# I2C_SW.net
KiCad netlist of a schematic drawn in Altium Designer
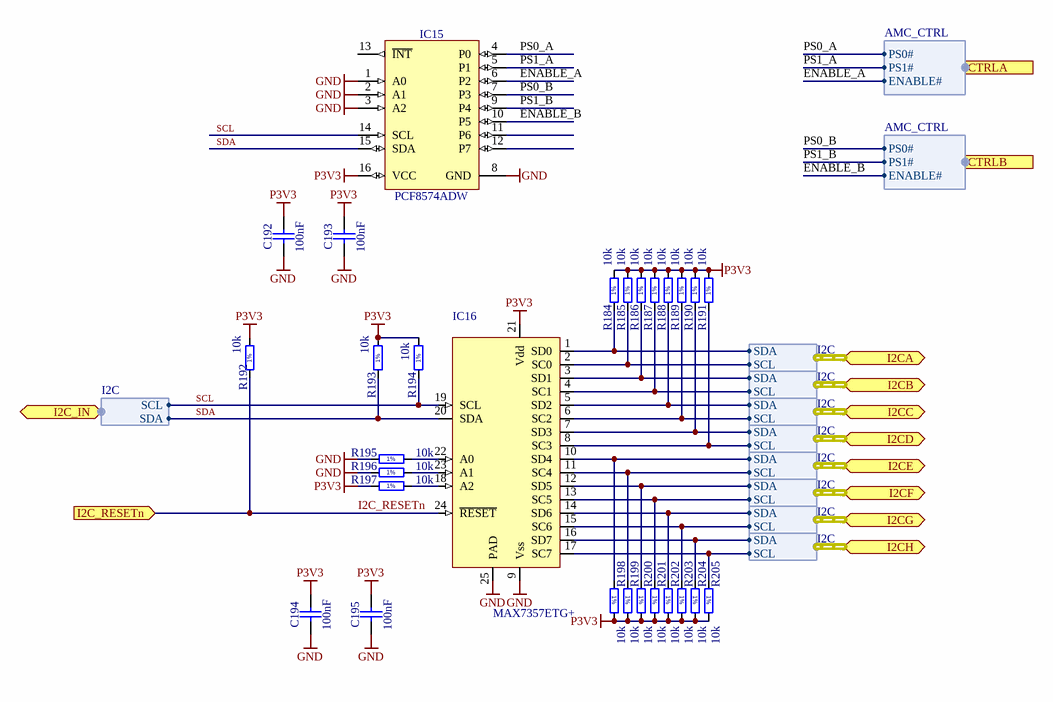
[diagram p0: I2C_SW.SchDoc]

(export (version "E")
  (design (tool "Eeschema 10.0.6"))
  (components
    (comp (ref "C192")
      (value "100nF")
      (footprint "CAPC0603X33N")
      (description "Non-polarised capacitor")
      (fields
        (field (name "PART NUMBER") "CC0201_100NF_6.3V_10%_X5R")
        (field (name "VOLTAGE") "6.3V")
        (field (name "AUTHOR") "CERN DEM JLC")
      )
      (libsource (lib "Capacitors") (part "Capacitor - non polarized"))
    )
    (comp (ref "C193")
      (value "100nF")
      (footprint "CAPC0603X33N")
      (description "Non-polarised capacitor")
      (fields
        (field (name "PART NUMBER") "CC0201_100NF_6.3V_10%_X5R")
        (field (name "VOLTAGE") "6.3V")
        (field (name "AUTHOR") "CERN DEM JLC")
      )
      (libsource (lib "Capacitors") (part "Capacitor - non polarized"))
    )
    (comp (ref "C194")
      (value "100nF")
      (footprint "CAPC0603X33N")
      (description "Non-polarised capacitor")
      (fields
        (field (name "PART NUMBER") "CC0201_100NF_6.3V_10%_X5R")
        (field (name "VOLTAGE") "6.3V")
        (field (name "AUTHOR") "CERN DEM JLC")
      )
      (libsource (lib "Capacitors") (part "Capacitor - non polarized"))
    )
    (comp (ref "C195")
      (value "100nF")
      (footprint "CAPC0603X33N")
      (description "Non-polarised capacitor")
      (fields
        (field (name "PART NUMBER") "CC0201_100NF_6.3V_10%_X5R")
        (field (name "VOLTAGE") "6.3V")
        (field (name "AUTHOR") "CERN DEM JLC")
      )
      (libsource (lib "Capacitors") (part "Capacitor - non polarized"))
    )
    (comp (ref "IC15")
      (value "PCF8574ADW")
      (footprint "SOIC127P1030X265-16N")
      (description "Remote 8-bit I/O Expander For I2C Bus")
      (fields (field (name "MANUFACTURER") "TEXAS INSTRUMENTS") (field (name "AUTHOR") "CERN DEM JLC"))
      (libsource (lib "ICs And Semiconductors") (part "PCF8574ADW"))
    )
    (comp (ref "IC16")
      (value "MAX7357ETG+")
      (footprint "HVQFN24")
      (description "8-channel I2C-bus multiplexer with reset, INT and timeout")
      (libsource (lib "LIBRARY_SCH") (part "IIC_MUX_MAX7357ETG+"))
    )
    (comp (ref "R184")
      (value "10k")
      (footprint "RESC1005X40N")
      (description "Resistor - 1%")
      (fields
        (field (name "PART NUMBER") "R0402_10K_1%_0.0625W_100PPM")
        (field (name "POWER") "0.0625W")
        (field (name "AUTHOR") "CERN DEM JLC")
      )
      (libsource (lib "Resistors") (part "Resistor - 1%"))
    )
    (comp (ref "R185")
      (value "10k")
      (footprint "RESC1005X40N")
      (description "Resistor - 1%")
      (fields
        (field (name "PART NUMBER") "R0402_10K_1%_0.0625W_100PPM")
        (field (name "POWER") "0.0625W")
        (field (name "AUTHOR") "CERN DEM JLC")
      )
      (libsource (lib "Resistors") (part "Resistor - 1%"))
    )
    (comp (ref "R186")
      (value "10k")
      (footprint "RESC1005X40N")
      (description "Resistor - 1%")
      (fields
        (field (name "PART NUMBER") "R0402_10K_1%_0.0625W_100PPM")
        (field (name "POWER") "0.0625W")
        (field (name "AUTHOR") "CERN DEM JLC")
      )
      (libsource (lib "Resistors") (part "Resistor - 1%"))
    )
    (comp (ref "R187")
      (value "10k")
      (footprint "RESC1005X40N")
      (description "Resistor - 1%")
      (fields
        (field (name "PART NUMBER") "R0402_10K_1%_0.0625W_100PPM")
        (field (name "POWER") "0.0625W")
        (field (name "AUTHOR") "CERN DEM JLC")
      )
      (libsource (lib "Resistors") (part "Resistor - 1%"))
    )
    (comp (ref "R188")
      (value "10k")
      (footprint "RESC1005X40N")
      (description "Resistor - 1%")
      (fields
        (field (name "PART NUMBER") "R0402_10K_1%_0.0625W_100PPM")
        (field (name "POWER") "0.0625W")
        (field (name "AUTHOR") "CERN DEM JLC")
      )
      (libsource (lib "Resistors") (part "Resistor - 1%"))
    )
    (comp (ref "R189")
      (value "10k")
      (footprint "RESC1005X40N")
      (description "Resistor - 1%")
      (fields
        (field (name "PART NUMBER") "R0402_10K_1%_0.0625W_100PPM")
        (field (name "POWER") "0.0625W")
        (field (name "AUTHOR") "CERN DEM JLC")
      )
      (libsource (lib "Resistors") (part "Resistor - 1%"))
    )
    (comp (ref "R190")
      (value "10k")
      (footprint "RESC1005X40N")
      (description "Resistor - 1%")
      (fields
        (field (name "PART NUMBER") "R0402_10K_1%_0.0625W_100PPM")
        (field (name "POWER") "0.0625W")
        (field (name "AUTHOR") "CERN DEM JLC")
      )
      (libsource (lib "Resistors") (part "Resistor - 1%"))
    )
    (comp (ref "R191")
      (value "10k")
      (footprint "RESC1005X40N")
      (description "Resistor - 1%")
      (fields
        (field (name "PART NUMBER") "R0402_10K_1%_0.0625W_100PPM")
        (field (name "POWER") "0.0625W")
        (field (name "AUTHOR") "CERN DEM JLC")
      )
      (libsource (lib "Resistors") (part "Resistor - 1%"))
    )
    (comp (ref "R192")
      (value "10k")
      (footprint "RESC1005X40N")
      (description "Resistor - 1%")
      (fields
        (field (name "PART NUMBER") "R0402_10K_1%_0.0625W_100PPM")
        (field (name "POWER") "0.0625W")
        (field (name "AUTHOR") "CERN DEM JLC")
      )
      (libsource (lib "Resistors") (part "Resistor - 1%"))
    )
    (comp (ref "R193")
      (value "10k")
      (footprint "RESC1005X40N")
      (description "Resistor - 1%")
      (fields
        (field (name "PART NUMBER") "R0402_10K_1%_0.0625W_100PPM")
        (field (name "POWER") "0.0625W")
        (field (name "AUTHOR") "CERN DEM JLC")
      )
      (libsource (lib "Resistors") (part "Resistor - 1%"))
    )
    (comp (ref "R194")
      (value "10k")
      (footprint "RESC1005X40N")
      (description "Resistor - 1%")
      (fields
        (field (name "PART NUMBER") "R0402_10K_1%_0.0625W_100PPM")
        (field (name "POWER") "0.0625W")
        (field (name "AUTHOR") "CERN DEM JLC")
      )
      (libsource (lib "Resistors") (part "Resistor - 1%"))
    )
    (comp (ref "R195")
      (value "10k")
      (footprint "RESC1005X40N")
      (description "Resistor - 1%")
      (fields
        (field (name "PART NUMBER") "R0402_10K_1%_0.0625W_100PPM")
        (field (name "POWER") "0.0625W")
        (field (name "AUTHOR") "CERN DEM JLC")
      )
      (libsource (lib "Resistors") (part "Resistor - 1%"))
    )
    (comp (ref "R196")
      (value "10k")
      (footprint "RESC1005X40N")
      (description "Resistor - 1%")
      (fields
        (field (name "PART NUMBER") "R0402_10K_1%_0.0625W_100PPM")
        (field (name "POWER") "0.0625W")
        (field (name "AUTHOR") "CERN DEM JLC")
      )
      (libsource (lib "Resistors") (part "Resistor - 1%"))
    )
    (comp (ref "R197")
      (value "10k")
      (footprint "RESC1005X40N")
      (description "Resistor - 1%")
      (fields
        (field (name "PART NUMBER") "R0402_10K_1%_0.0625W_100PPM")
        (field (name "POWER") "0.0625W")
        (field (name "AUTHOR") "CERN DEM JLC")
      )
      (libsource (lib "Resistors") (part "Resistor - 1%"))
    )
    (comp (ref "R198")
      (value "10k")
      (footprint "RESC1005X40N")
      (description "Resistor - 1%")
      (fields
        (field (name "PART NUMBER") "R0402_10K_1%_0.0625W_100PPM")
        (field (name "POWER") "0.0625W")
        (field (name "AUTHOR") "CERN DEM JLC")
      )
      (libsource (lib "Resistors") (part "Resistor - 1%"))
    )
    (comp (ref "R199")
      (value "10k")
      (footprint "RESC1005X40N")
      (description "Resistor - 1%")
      (fields
        (field (name "PART NUMBER") "R0402_10K_1%_0.0625W_100PPM")
        (field (name "POWER") "0.0625W")
        (field (name "AUTHOR") "CERN DEM JLC")
      )
      (libsource (lib "Resistors") (part "Resistor - 1%"))
    )
    (comp (ref "R200")
      (value "10k")
      (footprint "RESC1005X40N")
      (description "Resistor - 1%")
      (fields
        (field (name "PART NUMBER") "R0402_10K_1%_0.0625W_100PPM")
        (field (name "POWER") "0.0625W")
        (field (name "AUTHOR") "CERN DEM JLC")
      )
      (libsource (lib "Resistors") (part "Resistor - 1%"))
    )
    (comp (ref "R201")
      (value "10k")
      (footprint "RESC1005X40N")
      (description "Resistor - 1%")
      (fields
        (field (name "PART NUMBER") "R0402_10K_1%_0.0625W_100PPM")
        (field (name "POWER") "0.0625W")
        (field (name "AUTHOR") "CERN DEM JLC")
      )
      (libsource (lib "Resistors") (part "Resistor - 1%"))
    )
    (comp (ref "R202")
      (value "10k")
      (footprint "RESC1005X40N")
      (description "Resistor - 1%")
      (fields
        (field (name "PART NUMBER") "R0402_10K_1%_0.0625W_100PPM")
        (field (name "POWER") "0.0625W")
        (field (name "AUTHOR") "CERN DEM JLC")
      )
      (libsource (lib "Resistors") (part "Resistor - 1%"))
    )
    (comp (ref "R203")
      (value "10k")
      (footprint "RESC1005X40N")
      (description "Resistor - 1%")
      (fields
        (field (name "PART NUMBER") "R0402_10K_1%_0.0625W_100PPM")
        (field (name "POWER") "0.0625W")
        (field (name "AUTHOR") "CERN DEM JLC")
      )
      (libsource (lib "Resistors") (part "Resistor - 1%"))
    )
    (comp (ref "R204")
      (value "10k")
      (footprint "RESC1005X40N")
      (description "Resistor - 1%")
      (fields
        (field (name "PART NUMBER") "R0402_10K_1%_0.0625W_100PPM")
        (field (name "POWER") "0.0625W")
        (field (name "AUTHOR") "CERN DEM JLC")
      )
      (libsource (lib "Resistors") (part "Resistor - 1%"))
    )
    (comp (ref "R205")
      (value "10k")
      (footprint "RESC1005X40N")
      (description "Resistor - 1%")
      (fields
        (field (name "PART NUMBER") "R0402_10K_1%_0.0625W_100PPM")
        (field (name "POWER") "0.0625W")
        (field (name "AUTHOR") "CERN DEM JLC")
      )
      (libsource (lib "Resistors") (part "Resistor - 1%"))
    )
  )
  (nets
    (net (code "4") (name "/ENABLE_A") (class "Default")
      (node (ref "IC15") (pin "6") (pinfunction "P2_6") (pintype "bidirectional"))
    )
    (net (code "5") (name "/ENABLE_B") (class "Default")
      (node (ref "IC15") (pin "10") (pinfunction "P5_10") (pintype "bidirectional"))
    )
    (net (code "7") (name "/I2C_RESETn") (class "Default")
      (node (ref "IC16") (pin "24") (pinfunction "~{RESET}_24") (pintype "input"))
      (node (ref "R192") (pin "1") (pinfunction "1_1") (pintype "passive"))
    )
    (net (code "8") (name "/PS0_A") (class "Default")
      (node (ref "IC15") (pin "4") (pinfunction "P0_4") (pintype "bidirectional"))
    )
    (net (code "9") (name "/PS0_B") (class "Default")
      (node (ref "IC15") (pin "7") (pinfunction "P3_7") (pintype "bidirectional"))
    )
    (net (code "10") (name "/PS1_A") (class "Default")
      (node (ref "IC15") (pin "5") (pinfunction "P1_5") (pintype "bidirectional"))
    )
    (net (code "11") (name "/PS1_B") (class "Default")
      (node (ref "IC15") (pin "9") (pinfunction "P4_9") (pintype "bidirectional"))
    )
    (net (code "12") (name "/SCL") (class "Default")
      (node (ref "IC15") (pin "14") (pinfunction "SCL_14") (pintype "input"))
      (node (ref "IC16") (pin "19") (pinfunction "SCL_19") (pintype "input"))
      (node (ref "R194") (pin "1") (pinfunction "1_1") (pintype "passive"))
    )
    (net (code "13") (name "/SDA") (class "Default")
      (node (ref "IC15") (pin "15") (pinfunction "SDA_15") (pintype "bidirectional"))
      (node (ref "IC16") (pin "20") (pinfunction "SDA_20") (pintype "bidirectional"))
      (node (ref "R193") (pin "1") (pinfunction "1_1") (pintype "passive"))
    )
    (net (code "16") (name "GND") (class "Default")
      (node (ref "C192") (pin "1") (pinfunction "1_1") (pintype "passive"))
      (node (ref "C193") (pin "1") (pinfunction "1_1") (pintype "passive"))
      (node (ref "C194") (pin "1") (pinfunction "1_1") (pintype "passive"))
      (node (ref "C195") (pin "1") (pinfunction "1_1") (pintype "passive"))
      (node (ref "IC15") (pin "1") (pinfunction "A0_1") (pintype "input"))
      (node (ref "IC15") (pin "2") (pinfunction "A1_2") (pintype "input"))
      (node (ref "IC15") (pin "3") (pinfunction "A2_3") (pintype "input"))
      (node (ref "IC15") (pin "8") (pinfunction "GND_8") (pintype "power_in"))
      (node (ref "IC16") (pin "25") (pinfunction "PAD_25") (pintype "power_in"))
      (node (ref "IC16") (pin "9") (pinfunction "Vss_9") (pintype "power_in"))
      (node (ref "R195") (pin "1") (pinfunction "1_1") (pintype "passive"))
      (node (ref "R196") (pin "1") (pinfunction "1_1") (pintype "passive"))
    )
    (net (code "17") (name "Net-(IC16-A0)") (class "Default")
      (node (ref "IC16") (pin "22") (pinfunction "A0_22") (pintype "input"))
      (node (ref "R195") (pin "2") (pinfunction "2_2") (pintype "passive"))
    )
    (net (code "18") (name "Net-(IC16-A1)") (class "Default")
      (node (ref "IC16") (pin "23") (pinfunction "A1_23") (pintype "input"))
      (node (ref "R196") (pin "2") (pinfunction "2_2") (pintype "passive"))
    )
    (net (code "19") (name "Net-(IC16-A2)") (class "Default")
      (node (ref "IC16") (pin "18") (pinfunction "A2_18") (pintype "input"))
      (node (ref "R197") (pin "2") (pinfunction "2_2") (pintype "passive"))
    )
    (net (code "20") (name "Net-(IC16-SC0)") (class "Default")
      (node (ref "IC16") (pin "2") (pinfunction "SC0_2") (pintype "bidirectional"))
      (node (ref "R185") (pin "1") (pinfunction "1_1") (pintype "passive"))
    )
    (net (code "21") (name "Net-(IC16-SC1)") (class "Default")
      (node (ref "IC16") (pin "4") (pinfunction "SC1_4") (pintype "bidirectional"))
      (node (ref "R187") (pin "1") (pinfunction "1_1") (pintype "passive"))
    )
    (net (code "22") (name "Net-(IC16-SC2)") (class "Default")
      (node (ref "IC16") (pin "6") (pinfunction "SC2_6") (pintype "bidirectional"))
      (node (ref "R189") (pin "1") (pinfunction "1_1") (pintype "passive"))
    )
    (net (code "23") (name "Net-(IC16-SC3)") (class "Default")
      (node (ref "IC16") (pin "8") (pinfunction "SC3_8") (pintype "bidirectional"))
      (node (ref "R191") (pin "1") (pinfunction "1_1") (pintype "passive"))
    )
    (net (code "24") (name "Net-(IC16-SC4)") (class "Default")
      (node (ref "IC16") (pin "11") (pinfunction "SC4_11") (pintype "bidirectional"))
      (node (ref "R199") (pin "1") (pinfunction "1_1") (pintype "passive"))
    )
    (net (code "25") (name "Net-(IC16-SC5)") (class "Default")
      (node (ref "IC16") (pin "13") (pinfunction "SC5_13") (pintype "bidirectional"))
      (node (ref "R201") (pin "1") (pinfunction "1_1") (pintype "passive"))
    )
    (net (code "26") (name "Net-(IC16-SC6)") (class "Default")
      (node (ref "IC16") (pin "15") (pinfunction "SC6_15") (pintype "bidirectional"))
      (node (ref "R203") (pin "1") (pinfunction "1_1") (pintype "passive"))
    )
    (net (code "27") (name "Net-(IC16-SC7)") (class "Default")
      (node (ref "IC16") (pin "17") (pinfunction "SC7_17") (pintype "bidirectional"))
      (node (ref "R205") (pin "1") (pinfunction "1_1") (pintype "passive"))
    )
    (net (code "28") (name "Net-(IC16-SD0)") (class "Default")
      (node (ref "IC16") (pin "1") (pinfunction "SD0_1") (pintype "bidirectional"))
      (node (ref "R184") (pin "1") (pinfunction "1_1") (pintype "passive"))
    )
    (net (code "29") (name "Net-(IC16-SD1)") (class "Default")
      (node (ref "IC16") (pin "3") (pinfunction "SD1_3") (pintype "bidirectional"))
      (node (ref "R186") (pin "1") (pinfunction "1_1") (pintype "passive"))
    )
    (net (code "30") (name "Net-(IC16-SD2)") (class "Default")
      (node (ref "IC16") (pin "5") (pinfunction "SD2_5") (pintype "bidirectional"))
      (node (ref "R188") (pin "1") (pinfunction "1_1") (pintype "passive"))
    )
    (net (code "31") (name "Net-(IC16-SD3)") (class "Default")
      (node (ref "IC16") (pin "7") (pinfunction "SD3_7") (pintype "bidirectional"))
      (node (ref "R190") (pin "1") (pinfunction "1_1") (pintype "passive"))
    )
    (net (code "32") (name "Net-(IC16-SD4)") (class "Default")
      (node (ref "IC16") (pin "10") (pinfunction "SD4_10") (pintype "bidirectional"))
      (node (ref "R198") (pin "1") (pinfunction "1_1") (pintype "passive"))
    )
    (net (code "33") (name "Net-(IC16-SD5)") (class "Default")
      (node (ref "IC16") (pin "12") (pinfunction "SD5_12") (pintype "bidirectional"))
      (node (ref "R200") (pin "1") (pinfunction "1_1") (pintype "passive"))
    )
    (net (code "34") (name "Net-(IC16-SD6)") (class "Default")
      (node (ref "IC16") (pin "14") (pinfunction "SD6_14") (pintype "bidirectional"))
      (node (ref "R202") (pin "1") (pinfunction "1_1") (pintype "passive"))
    )
    (net (code "35") (name "Net-(IC16-SD7)") (class "Default")
      (node (ref "IC16") (pin "16") (pinfunction "SD7_16") (pintype "bidirectional"))
      (node (ref "R204") (pin "1") (pinfunction "1_1") (pintype "passive"))
    )
    (net (code "36") (name "P3V3") (class "Default")
      (node (ref "C192") (pin "2") (pinfunction "2_2") (pintype "passive"))
      (node (ref "C193") (pin "2") (pinfunction "2_2") (pintype "passive"))
      (node (ref "C194") (pin "2") (pinfunction "2_2") (pintype "passive"))
      (node (ref "C195") (pin "2") (pinfunction "2_2") (pintype "passive"))
      (node (ref "IC15") (pin "16") (pinfunction "VCC_16") (pintype "bidirectional"))
      (node (ref "IC16") (pin "21") (pinfunction "Vdd_21") (pintype "power_in"))
      (node (ref "R184") (pin "2") (pinfunction "2_2") (pintype "passive"))
      (node (ref "R185") (pin "2") (pinfunction "2_2") (pintype "passive"))
      (node (ref "R186") (pin "2") (pinfunction "2_2") (pintype "passive"))
      (node (ref "R187") (pin "2") (pinfunction "2_2") (pintype "passive"))
      (node (ref "R188") (pin "2") (pinfunction "2_2") (pintype "passive"))
      (node (ref "R189") (pin "2") (pinfunction "2_2") (pintype "passive"))
      (node (ref "R190") (pin "2") (pinfunction "2_2") (pintype "passive"))
      (node (ref "R191") (pin "2") (pinfunction "2_2") (pintype "passive"))
      (node (ref "R192") (pin "2") (pinfunction "2_2") (pintype "passive"))
      (node (ref "R193") (pin "2") (pinfunction "2_2") (pintype "passive"))
      (node (ref "R194") (pin "2") (pinfunction "2_2") (pintype "passive"))
      (node (ref "R197") (pin "1") (pinfunction "1_1") (pintype "passive"))
      (node (ref "R198") (pin "2") (pinfunction "2_2") (pintype "passive"))
      (node (ref "R199") (pin "2") (pinfunction "2_2") (pintype "passive"))
      (node (ref "R200") (pin "2") (pinfunction "2_2") (pintype "passive"))
      (node (ref "R201") (pin "2") (pinfunction "2_2") (pintype "passive"))
      (node (ref "R202") (pin "2") (pinfunction "2_2") (pintype "passive"))
      (node (ref "R203") (pin "2") (pinfunction "2_2") (pintype "passive"))
      (node (ref "R204") (pin "2") (pinfunction "2_2") (pintype "passive"))
      (node (ref "R205") (pin "2") (pinfunction "2_2") (pintype "passive"))
    )
    (net (code "37") (name "unconnected-(IC15-P6-Pad11)") (class "Default")
      (node (ref "IC15") (pin "11") (pinfunction "P6_11") (pintype "bidirectional"))
    )
    (net (code "38") (name "unconnected-(IC15-P7-Pad12)") (class "Default")
      (node (ref "IC15") (pin "12") (pinfunction "P7_12") (pintype "bidirectional"))
    )
    (net (code "39") (name "unconnected-(IC15-~{INT}-Pad13)") (class "Default")
      (node (ref "IC15") (pin "13") (pinfunction "~{INT}_13") (pintype "output"))
    )
  )
)
